# 03_Dimmer.net
KiCad netlist of a schematic drawn in Altium Designer
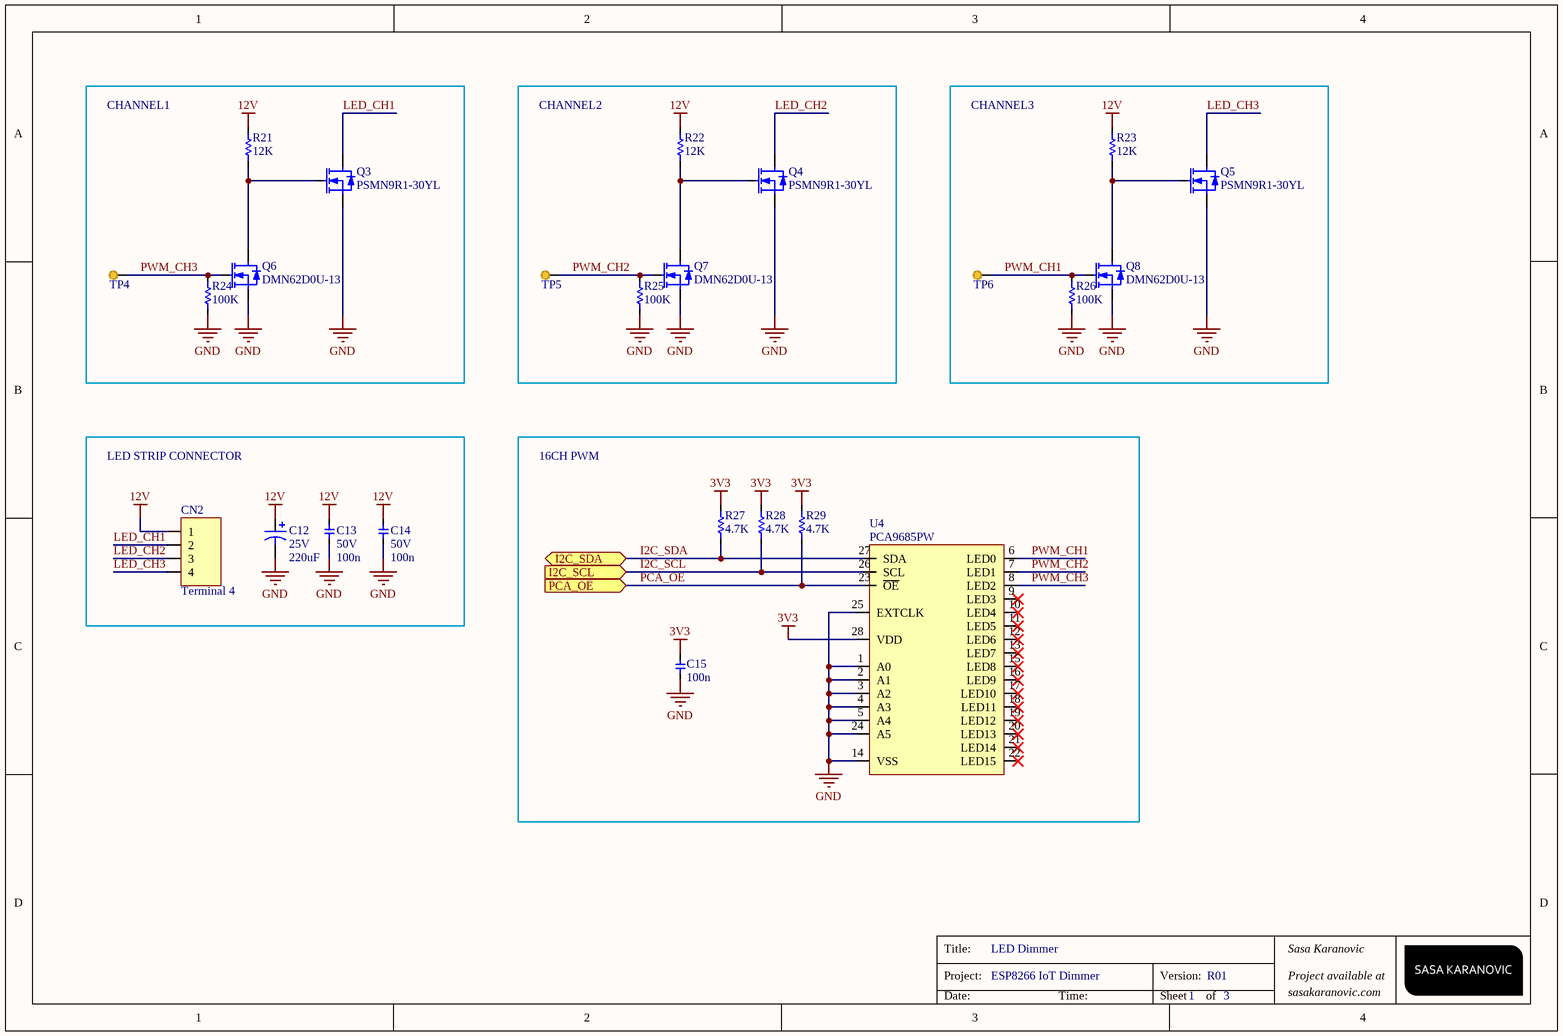
[diagram p0: 03_Dimmer.SchDoc]

(export (version "E")
  (design (tool "Eeschema 10.0.6"))
  (components
    (comp (ref "C12")
      (value "25V")
      (footprint "Moji Footprintovi:Electrolytic Cap 2.54mm")
      (description "Polarized Capacitor (Axial)")
      (fields
        (field (name "MANUFACTURER") "Yageo")
        (field (name "MANUFACTURER PART NUMBER") "AC0603FR-07470RL")
        (field (name "ALTIUM_VALUE") "220uF")
      )
      (libsource (lib "Moji Schematici") (part "Cap Electrolytic"))
    )
    (comp (ref "C13")
      (value "50V")
      (footprint "Moji Footprintovi:0603 - CAP")
      (description "Capacitor")
      (fields
        (field (name "MANUFACTURER") "AVX Corporation")
        (field (name "MANUFACTURER PART NUMBER") "06035C104KAT2A")
        (field (name "ALTIUM_VALUE") "100n")
      )
      (libsource (lib "Moji Schematici") (part "Cap"))
    )
    (comp (ref "C14")
      (value "50V")
      (footprint "Moji Footprintovi:0603 - CAP")
      (description "Capacitor")
      (fields
        (field (name "MANUFACTURER") "AVX Corporation")
        (field (name "MANUFACTURER PART NUMBER") "06035C104KAT2A")
        (field (name "ALTIUM_VALUE") "100n")
      )
      (libsource (lib "Moji Schematici") (part "Cap"))
    )
    (comp (ref "C15")
      (value "100n")
      (footprint "Moji Footprintovi:0603 - CAP")
      (description "Capacitor")
      (fields
        (field (name "MANUFACTURER") "AVX Corporation")
        (field (name "MANUFACTURER PART NUMBER") "06035C104KAT2A")
      )
      (libsource (lib "Moji Schematici") (part "Cap"))
    )
    (comp (ref "CN2")
      (value "Terminal 4")
      (footprint "Moji Footprintovi:Terminal 4_90DEG")
      (description "TERM BLOCK PCB 4POS 5.0MM GREEN")
      (fields
        (field (name "DISTRIBUTOR PART NUMBER") "277-1579-ND")
        (field (name "MANUFACTURER") "Phoenix Contact")
      )
      (libsource (lib "Moji Schematici") (part "Terminal 4"))
    )
    (comp (ref "Q3")
      (value "PSMN9R1-30YL")
      (footprint "Moji Footprintovi:LFPAK-8")
      (description "MOSFET N-CH 30V 37A LFPAK")
      (fields
        (field (name "MANUFACTURER") "Nexperia USA Inc.")
        (field (name "MANUFACTURER PART NUMBER") "PSMN011-30YLC,115")
      )
      (libsource (lib "Moji Schematici") (part "PSMN9R1-30YL"))
    )
    (comp (ref "Q4")
      (value "PSMN9R1-30YL")
      (footprint "Moji Footprintovi:LFPAK-8")
      (description "MOSFET N-CH 30V 37A LFPAK")
      (fields
        (field (name "MANUFACTURER") "Nexperia USA Inc.")
        (field (name "MANUFACTURER PART NUMBER") "PSMN011-30YLC,115")
      )
      (libsource (lib "Moji Schematici") (part "PSMN9R1-30YL"))
    )
    (comp (ref "Q5")
      (value "PSMN9R1-30YL")
      (footprint "Moji Footprintovi:LFPAK-8")
      (description "MOSFET N-CH 30V 37A LFPAK")
      (fields
        (field (name "MANUFACTURER") "Nexperia USA Inc.")
        (field (name "MANUFACTURER PART NUMBER") "PSMN011-30YLC,115")
      )
      (libsource (lib "Moji Schematici") (part "PSMN9R1-30YL"))
    )
    (comp (ref "Q6")
      (value "DMN62D0U-13")
      (footprint "Moji Footprintovi:SOT90P240X100-3N")
      (description "MOSFET N-CH 60V 0.38A")
      (fields
        (field (name "MANUFACTURER") "Diodes Incorporated")
        (field (name "DISTRIBUTOR PART NUMBER") "DMN62D0U-13DICT-ND")
      )
      (libsource (lib "Moji Schematici") (part "DMN62D0U-13"))
    )
    (comp (ref "Q7")
      (value "DMN62D0U-13")
      (footprint "Moji Footprintovi:SOT90P240X100-3N")
      (description "MOSFET N-CH 60V 0.38A")
      (fields
        (field (name "MANUFACTURER") "Diodes Incorporated")
        (field (name "DISTRIBUTOR PART NUMBER") "DMN62D0U-13DICT-ND")
      )
      (libsource (lib "Moji Schematici") (part "DMN62D0U-13"))
    )
    (comp (ref "Q8")
      (value "DMN62D0U-13")
      (footprint "Moji Footprintovi:SOT90P240X100-3N")
      (description "MOSFET N-CH 60V 0.38A")
      (fields
        (field (name "MANUFACTURER") "Diodes Incorporated")
        (field (name "DISTRIBUTOR PART NUMBER") "DMN62D0U-13DICT-ND")
      )
      (libsource (lib "Moji Schematici") (part "DMN62D0U-13"))
    )
    (comp (ref "R21")
      (value "12K")
      (footprint "Moji Footprintovi:0603")
      (description "Resistor")
      (fields
        (field (name "MANUFACTURER") "Yageo")
        (field (name "MANUFACTURER PART NUMBER") "RT0603FRE0712KL")
      )
      (libsource (lib "Moji Schematici") (part "Res"))
    )
    (comp (ref "R22")
      (value "12K")
      (footprint "Moji Footprintovi:0603")
      (description "Resistor")
      (fields
        (field (name "MANUFACTURER") "Yageo")
        (field (name "MANUFACTURER PART NUMBER") "RT0603FRE0712KL")
      )
      (libsource (lib "Moji Schematici") (part "Res"))
    )
    (comp (ref "R23")
      (value "12K")
      (footprint "Moji Footprintovi:0603")
      (description "Resistor")
      (fields
        (field (name "MANUFACTURER") "Yageo")
        (field (name "MANUFACTURER PART NUMBER") "RT0603FRE0712KL")
      )
      (libsource (lib "Moji Schematici") (part "Res"))
    )
    (comp (ref "R24")
      (value "100K")
      (footprint "Moji Footprintovi:0603")
      (description "Resistor")
      (fields
        (field (name "MANUFACTURER") "Yageo")
        (field (name "MANUFACTURER PART NUMBER") "RT0603BRD07100KL")
      )
      (libsource (lib "Moji Schematici") (part "Res"))
    )
    (comp (ref "R25")
      (value "100K")
      (footprint "Moji Footprintovi:0603")
      (description "Resistor")
      (fields
        (field (name "MANUFACTURER") "Yageo")
        (field (name "MANUFACTURER PART NUMBER") "RT0603BRD07100KL")
      )
      (libsource (lib "Moji Schematici") (part "Res"))
    )
    (comp (ref "R26")
      (value "100K")
      (footprint "Moji Footprintovi:0603")
      (description "Resistor")
      (fields
        (field (name "MANUFACTURER") "Yageo")
        (field (name "MANUFACTURER PART NUMBER") "RT0603BRD07100KL")
      )
      (libsource (lib "Moji Schematici") (part "Res"))
    )
    (comp (ref "R27")
      (value "4.7K")
      (footprint "Moji Footprintovi:0603")
      (description "Resistor")
      (fields
        (field (name "MANUFACTURER") "Yageo")
        (field (name "MANUFACTURER PART NUMBER") "RT0603FRE074K7L")
      )
      (libsource (lib "Moji Schematici") (part "Res"))
    )
    (comp (ref "R28")
      (value "4.7K")
      (footprint "Moji Footprintovi:0603")
      (description "Resistor")
      (fields
        (field (name "MANUFACTURER") "Yageo")
        (field (name "MANUFACTURER PART NUMBER") "RT0603FRE074K7L")
      )
      (libsource (lib "Moji Schematici") (part "Res"))
    )
    (comp (ref "R29")
      (value "4.7K")
      (footprint "Moji Footprintovi:0603")
      (description "Resistor")
      (fields
        (field (name "MANUFACTURER") "Yageo")
        (field (name "MANUFACTURER PART NUMBER") "RT0603FRE074K7L")
      )
      (libsource (lib "Moji Schematici") (part "Res"))
    )
    (comp (ref "TP4")
      (value "Test Point 0.6mm")
      (footprint "Moji Footprintovi:TP_SMD_1mm")
      (libsource (lib "Moji Schematici") (part "TP"))
    )
    (comp (ref "TP5")
      (value "Test Point 0.6mm")
      (footprint "Moji Footprintovi:TP_SMD_1mm")
      (libsource (lib "Moji Schematici") (part "TP"))
    )
    (comp (ref "TP6")
      (value "Test Point 0.6mm")
      (footprint "Moji Footprintovi:TP_SMD_1mm")
      (libsource (lib "Moji Schematici") (part "TP"))
    )
    (comp (ref "U4")
      (value "PCA9685PW")
      (footprint "Moji Footprintovi:TSOP65P640X100-28N")
      (description "IC LED DRIVER RGBA 28-TSSOP")
      (fields
        (field (name "MANUFACTURER") "NXP USA Inc.")
        (field (name "MANUFACTURER PART NUMBER") "PCA9685PW,118")
      )
      (libsource (lib "Moji Schematici") (part "PCA9685"))
    )
  )
  (nets
    (net (code "1") (name "/I2C_SCL") (class "Default")
      (node (ref "R28") (pin "1") (pinfunction "1_1") (pintype "passive"))
      (node (ref "U4") (pin "26") (pinfunction "SCL_26") (pintype "passive"))
    )
    (net (code "2") (name "/I2C_SDA") (class "Default")
      (node (ref "R27") (pin "1") (pinfunction "1_1") (pintype "passive"))
      (node (ref "U4") (pin "27") (pinfunction "SDA_27") (pintype "passive"))
    )
    (net (code "3") (name "/LED_CH1") (class "Default")
      (node (ref "CN2") (pin "2") (pinfunction "2_2") (pintype "passive"))
      (node (ref "Q3") (pin "D") (pinfunction "D_D") (pintype "passive"))
    )
    (net (code "4") (name "/LED_CH2") (class "Default")
      (node (ref "CN2") (pin "3") (pinfunction "3_3") (pintype "passive"))
      (node (ref "Q4") (pin "D") (pinfunction "D_D") (pintype "passive"))
    )
    (net (code "5") (name "/LED_CH3") (class "Default")
      (node (ref "CN2") (pin "4") (pinfunction "4_4") (pintype "passive"))
      (node (ref "Q5") (pin "D") (pinfunction "D_D") (pintype "passive"))
    )
    (net (code "6") (name "/PCA_OE") (class "Default")
      (node (ref "R29") (pin "1") (pinfunction "1_1") (pintype "passive"))
      (node (ref "U4") (pin "23") (pinfunction "~{OE}_23") (pintype "passive"))
    )
    (net (code "7") (name "/PWM_CH1") (class "Default")
      (node (ref "Q8") (pin "1") (pinfunction "G_1") (pintype "passive"))
      (node (ref "R26") (pin "2") (pinfunction "2_2") (pintype "passive"))
      (node (ref "TP6") (pin "1") (pinfunction "1_1") (pintype "passive"))
      (node (ref "U4") (pin "6") (pinfunction "LED0_6") (pintype "passive"))
    )
    (net (code "8") (name "/PWM_CH2") (class "Default")
      (node (ref "Q7") (pin "1") (pinfunction "G_1") (pintype "passive"))
      (node (ref "R25") (pin "2") (pinfunction "2_2") (pintype "passive"))
      (node (ref "TP5") (pin "1") (pinfunction "1_1") (pintype "passive"))
      (node (ref "U4") (pin "7") (pinfunction "LED1_7") (pintype "passive"))
    )
    (net (code "9") (name "/PWM_CH3") (class "Default")
      (node (ref "Q6") (pin "1") (pinfunction "G_1") (pintype "passive"))
      (node (ref "R24") (pin "2") (pinfunction "2_2") (pintype "passive"))
      (node (ref "TP4") (pin "1") (pinfunction "1_1") (pintype "passive"))
      (node (ref "U4") (pin "8") (pinfunction "LED2_8") (pintype "passive"))
    )
    (net (code "10") (name "3V3") (class "Default")
      (node (ref "C15") (pin "2") (pinfunction "2_2") (pintype "passive"))
      (node (ref "R27") (pin "2") (pinfunction "2_2") (pintype "passive"))
      (node (ref "R28") (pin "2") (pinfunction "2_2") (pintype "passive"))
      (node (ref "R29") (pin "2") (pinfunction "2_2") (pintype "passive"))
      (node (ref "U4") (pin "28") (pinfunction "VDD_28") (pintype "passive"))
    )
    (net (code "11") (name "12V") (class "Default")
      (node (ref "C12") (pin "1") (pinfunction "1_1") (pintype "passive"))
      (node (ref "C13") (pin "2") (pinfunction "2_2") (pintype "passive"))
      (node (ref "C14") (pin "2") (pinfunction "2_2") (pintype "passive"))
      (node (ref "CN2") (pin "1") (pinfunction "1_1") (pintype "passive"))
      (node (ref "R21") (pin "2") (pinfunction "2_2") (pintype "passive"))
      (node (ref "R22") (pin "2") (pinfunction "2_2") (pintype "passive"))
      (node (ref "R23") (pin "2") (pinfunction "2_2") (pintype "passive"))
    )
    (net (code "12") (name "GND") (class "Default")
      (node (ref "C12") (pin "2") (pinfunction "2_2") (pintype "passive"))
      (node (ref "C13") (pin "1") (pinfunction "1_1") (pintype "passive"))
      (node (ref "C14") (pin "1") (pinfunction "1_1") (pintype "passive"))
      (node (ref "C15") (pin "1") (pinfunction "1_1") (pintype "passive"))
      (node (ref "Q3") (pin "S") (pinfunction "S_S") (pintype "passive"))
      (node (ref "Q4") (pin "S") (pinfunction "S_S") (pintype "passive"))
      (node (ref "Q5") (pin "S") (pinfunction "S_S") (pintype "passive"))
      (node (ref "Q6") (pin "3") (pinfunction "S_3") (pintype "passive"))
      (node (ref "Q7") (pin "3") (pinfunction "S_3") (pintype "passive"))
      (node (ref "Q8") (pin "3") (pinfunction "S_3") (pintype "passive"))
      (node (ref "R24") (pin "1") (pinfunction "1_1") (pintype "passive"))
      (node (ref "R25") (pin "1") (pinfunction "1_1") (pintype "passive"))
      (node (ref "R26") (pin "1") (pinfunction "1_1") (pintype "passive"))
      (node (ref "U4") (pin "1") (pinfunction "A0_1") (pintype "passive"))
      (node (ref "U4") (pin "14") (pinfunction "VSS_14") (pintype "passive"))
      (node (ref "U4") (pin "2") (pinfunction "A1_2") (pintype "passive"))
      (node (ref "U4") (pin "24") (pinfunction "A5_24") (pintype "passive"))
      (node (ref "U4") (pin "25") (pinfunction "EXTCLK_25") (pintype "passive"))
      (node (ref "U4") (pin "3") (pinfunction "A2_3") (pintype "passive"))
      (node (ref "U4") (pin "4") (pinfunction "A3_4") (pintype "passive"))
      (node (ref "U4") (pin "5") (pinfunction "A4_5") (pintype "passive"))
    )
    (net (code "13") (name "Net-(Q6-D)") (class "Default")
      (node (ref "Q3") (pin "G") (pinfunction "G_G") (pintype "passive"))
      (node (ref "Q6") (pin "2") (pinfunction "D_2") (pintype "passive"))
      (node (ref "R21") (pin "1") (pinfunction "1_1") (pintype "passive"))
    )
    (net (code "14") (name "Net-(Q7-D)") (class "Default")
      (node (ref "Q4") (pin "G") (pinfunction "G_G") (pintype "passive"))
      (node (ref "Q7") (pin "2") (pinfunction "D_2") (pintype "passive"))
      (node (ref "R22") (pin "1") (pinfunction "1_1") (pintype "passive"))
    )
    (net (code "15") (name "Net-(Q8-D)") (class "Default")
      (node (ref "Q5") (pin "G") (pinfunction "G_G") (pintype "passive"))
      (node (ref "Q8") (pin "2") (pinfunction "D_2") (pintype "passive"))
      (node (ref "R23") (pin "1") (pinfunction "1_1") (pintype "passive"))
    )
    (net (code "16") (name "unconnected-(U4-LED3-Pad9)") (class "Default")
      (node (ref "U4") (pin "9") (pinfunction "LED3_9") (pintype "passive+no_connect"))
    )
    (net (code "17") (name "unconnected-(U4-LED4-Pad10)") (class "Default")
      (node (ref "U4") (pin "10") (pinfunction "LED4_10") (pintype "passive+no_connect"))
    )
    (net (code "18") (name "unconnected-(U4-LED5-Pad11)") (class "Default")
      (node (ref "U4") (pin "11") (pinfunction "LED5_11") (pintype "passive+no_connect"))
    )
    (net (code "19") (name "unconnected-(U4-LED6-Pad12)") (class "Default")
      (node (ref "U4") (pin "12") (pinfunction "LED6_12") (pintype "passive+no_connect"))
    )
    (net (code "20") (name "unconnected-(U4-LED7-Pad13)") (class "Default")
      (node (ref "U4") (pin "13") (pinfunction "LED7_13") (pintype "passive+no_connect"))
    )
    (net (code "21") (name "unconnected-(U4-LED8-Pad15)") (class "Default")
      (node (ref "U4") (pin "15") (pinfunction "LED8_15") (pintype "passive+no_connect"))
    )
    (net (code "22") (name "unconnected-(U4-LED9-Pad16)") (class "Default")
      (node (ref "U4") (pin "16") (pinfunction "LED9_16") (pintype "passive+no_connect"))
    )
    (net (code "23") (name "unconnected-(U4-LED10-Pad17)") (class "Default")
      (node (ref "U4") (pin "17") (pinfunction "LED10_17") (pintype "passive+no_connect"))
    )
    (net (code "24") (name "unconnected-(U4-LED11-Pad18)") (class "Default")
      (node (ref "U4") (pin "18") (pinfunction "LED11_18") (pintype "passive+no_connect"))
    )
    (net (code "25") (name "unconnected-(U4-LED12-Pad19)") (class "Default")
      (node (ref "U4") (pin "19") (pinfunction "LED12_19") (pintype "passive+no_connect"))
    )
    (net (code "26") (name "unconnected-(U4-LED13-Pad20)") (class "Default")
      (node (ref "U4") (pin "20") (pinfunction "LED13_20") (pintype "passive+no_connect"))
    )
    (net (code "27") (name "unconnected-(U4-LED14-Pad21)") (class "Default")
      (node (ref "U4") (pin "21") (pinfunction "LED14_21") (pintype "passive+no_connect"))
    )
    (net (code "28") (name "unconnected-(U4-LED15-Pad22)") (class "Default")
      (node (ref "U4") (pin "22") (pinfunction "LED15_22") (pintype "passive+no_connect"))
    )
  )
)
